# cortina.net
KiCad netlist of a schematic drawn in EAGLE
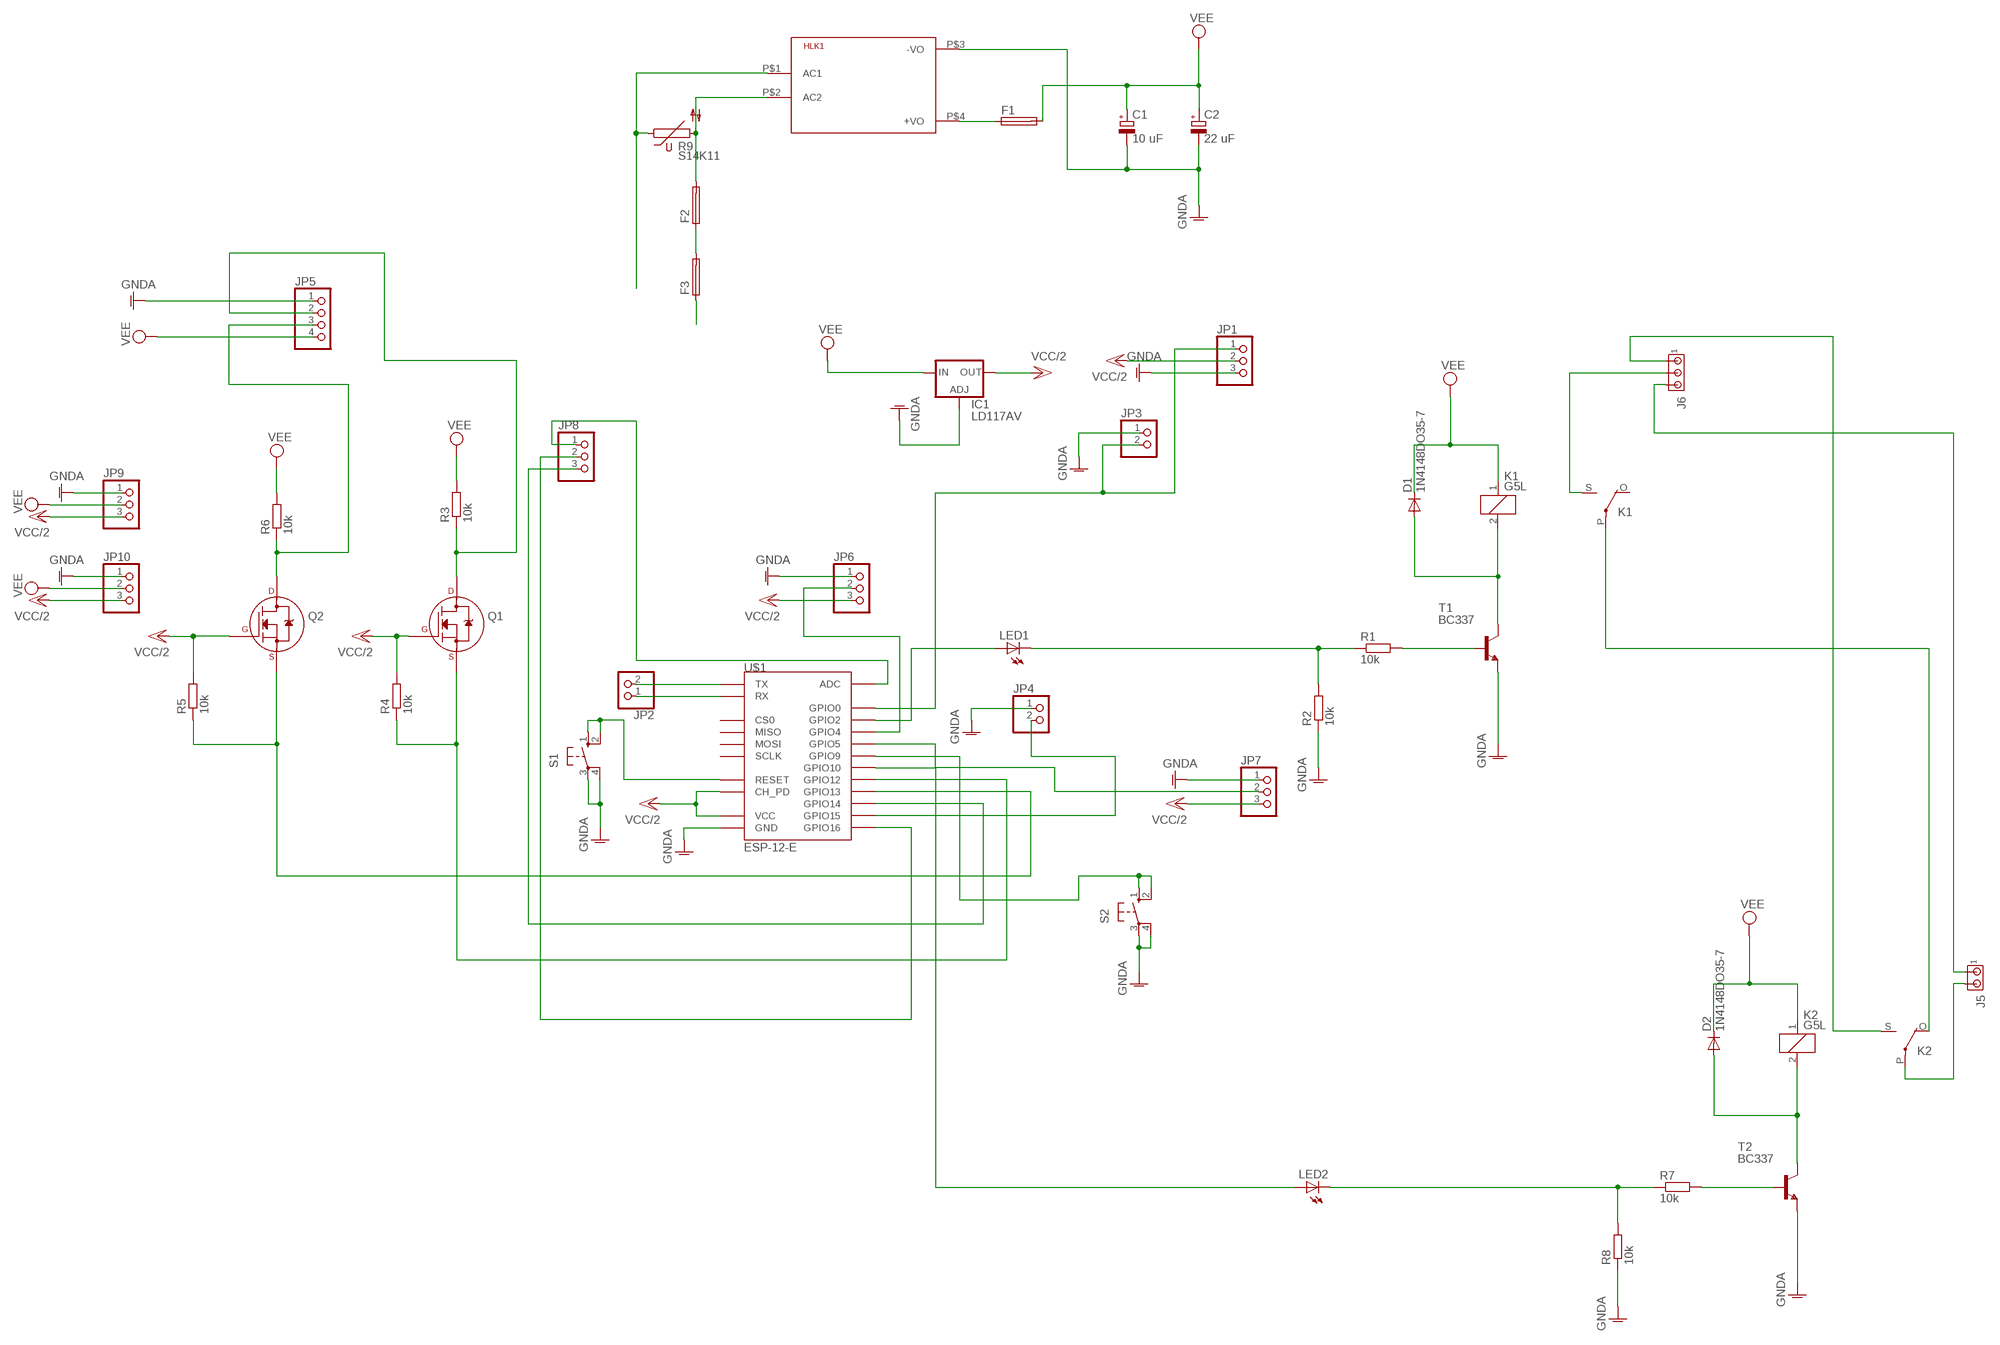
[diagram p0: schematic, sheet 1]

(export (version "E")
  (design (tool "Eeschema 10.0.6"))
  (components
    (comp (ref "C1")
      (value "10 uF")
      (footprint "eagle-import:E1,8-4")
      (libsource (lib "eagle-import") (part "CPOL-EUE1.8-4"))
    )
    (comp (ref "C2")
      (value "22 uF")
      (footprint "eagle-import:E1,8-4")
      (libsource (lib "eagle-import") (part "CPOL-EUE1.8-4"))
    )
    (comp (ref "D1")
      (value "1N4148DO35-7")
      (footprint "eagle-import:DO35-7")
      (libsource (lib "eagle-import") (part "1N4148DO35-7"))
    )
    (comp (ref "D2")
      (value "1N4148DO35-7")
      (footprint "eagle-import:DO35-7")
      (libsource (lib "eagle-import") (part "1N4148DO35-7"))
    )
    (comp (ref "F1")
      (value "GSH15")
      (footprint "eagle-import:GSH15")
      (fields (field (name "MPN") "64900001039"))
      (libsource (lib "eagle-import") (part "GSH15"))
    )
    (comp (ref "F2")
      (value "GSH15")
      (footprint "eagle-import:GSH15")
      (fields (field (name "MPN") "64900001039"))
      (libsource (lib "eagle-import") (part "GSH15"))
    )
    (comp (ref "F3")
      (value "GSH15")
      (footprint "eagle-import:GSH15")
      (fields (field (name "MPN") "64900001039"))
      (libsource (lib "eagle-import") (part "GSH15"))
    )
    (comp (ref "HLK1")
      (value "HLK-PM013W")
      (footprint "eagle-import:HLK-PM01")
      (libsource (lib "eagle-import") (part "HLK-PM013W"))
    )
    (comp (ref "IC1")
      (value "LD117AV")
      (footprint "eagle-import:TO220L1")
      (libsource (lib "eagle-import") (part "LD117A?V"))
    )
    (comp (ref "J5")
      (value "MTA02-156")
      (footprint "eagle-import:1X2MTA")
      (libsource (lib "eagle-import") (part "MTA02-156"))
    )
    (comp (ref "J6")
      (value "MTA03-156")
      (footprint "eagle-import:1X3MTA")
      (libsource (lib "eagle-import") (part "MTA03-156"))
    )
    (comp (ref "JP1")
      (value "PINHD-1X3")
      (footprint "eagle-import:1X03")
      (libsource (lib "eagle-import") (part "PINHD-1X3"))
    )
    (comp (ref "JP2")
      (value "PINHD-1X2")
      (footprint "eagle-import:1X02")
      (libsource (lib "eagle-import") (part "PINHD-1X2"))
    )
    (comp (ref "JP3")
      (value "PINHD-1X2")
      (footprint "eagle-import:1X02")
      (libsource (lib "eagle-import") (part "PINHD-1X2"))
    )
    (comp (ref "JP4")
      (value "PINHD-1X2")
      (footprint "eagle-import:1X02")
      (libsource (lib "eagle-import") (part "PINHD-1X2"))
    )
    (comp (ref "JP5")
      (value "PINHD-1X4")
      (footprint "eagle-import:1X04")
      (libsource (lib "eagle-import") (part "PINHD-1X4"))
    )
    (comp (ref "JP6")
      (value "PINHD-1X3")
      (footprint "eagle-import:1X03")
      (libsource (lib "eagle-import") (part "PINHD-1X3"))
    )
    (comp (ref "JP7")
      (value "PINHD-1X3")
      (footprint "eagle-import:1X03")
      (libsource (lib "eagle-import") (part "PINHD-1X3"))
    )
    (comp (ref "JP8")
      (value "PINHD-1X3")
      (footprint "eagle-import:1X03")
      (libsource (lib "eagle-import") (part "PINHD-1X3"))
    )
    (comp (ref "JP9")
      (value "PINHD-1X3")
      (footprint "eagle-import:1X03")
      (libsource (lib "eagle-import") (part "PINHD-1X3"))
    )
    (comp (ref "JP10")
      (value "PINHD-1X3")
      (footprint "eagle-import:1X03")
      (libsource (lib "eagle-import") (part "PINHD-1X3"))
    )
    (comp (ref "K1")
      (value "G5L")
      (footprint "eagle-import:G5LE")
      (libsource (lib "eagle-import") (part "G5L"))
    )
    (comp (ref "K2")
      (value "G5L")
      (footprint "eagle-import:G5LE")
      (libsource (lib "eagle-import") (part "G5L"))
    )
    (comp (ref "LED1")
      (value "LED5MM")
      (footprint "eagle-import:LED5MM")
      (libsource (lib "eagle-import") (part "LED5MM"))
    )
    (comp (ref "LED2")
      (value "LED5MM")
      (footprint "eagle-import:LED5MM")
      (libsource (lib "eagle-import") (part "LED5MM"))
    )
    (comp (ref "Q1")
      (value "2N7002_TO92")
      (footprint "eagle-import:TO-92")
      (libsource (lib "eagle-import") (part "2N700_TO922"))
    )
    (comp (ref "Q2")
      (value "2N7002_TO92")
      (footprint "eagle-import:TO-92")
      (libsource (lib "eagle-import") (part "2N700_TO922"))
    )
    (comp (ref "R1")
      (value "10k")
      (footprint "eagle-import:0207_7")
      (libsource (lib "eagle-import") (part "R-EU_0207/7"))
    )
    (comp (ref "R2")
      (value "10k")
      (footprint "eagle-import:0207_7")
      (libsource (lib "eagle-import") (part "R-EU_0207/7"))
    )
    (comp (ref "R3")
      (value "10k")
      (footprint "eagle-import:0207_7")
      (libsource (lib "eagle-import") (part "R-EU_0207/7"))
    )
    (comp (ref "R4")
      (value "10k")
      (footprint "eagle-import:0207_7")
      (libsource (lib "eagle-import") (part "R-EU_0207/7"))
    )
    (comp (ref "R5")
      (value "10k")
      (footprint "eagle-import:0207_7")
      (libsource (lib "eagle-import") (part "R-EU_0207/7"))
    )
    (comp (ref "R6")
      (value "10k")
      (footprint "eagle-import:0207_7")
      (libsource (lib "eagle-import") (part "R-EU_0207/7"))
    )
    (comp (ref "R7")
      (value "10k")
      (footprint "eagle-import:0207_7")
      (libsource (lib "eagle-import") (part "R-EU_0207/7"))
    )
    (comp (ref "R8")
      (value "10k")
      (footprint "eagle-import:0207_7")
      (libsource (lib "eagle-import") (part "R-EU_0207/7"))
    )
    (comp (ref "R9")
      (value "S14K11")
      (footprint "eagle-import:S14K11")
      (libsource (lib "eagle-import") (part "S14K11"))
    )
    (comp (ref "S1")
      (value "10-XX")
      (footprint "eagle-import:B3F-10XX")
      (fields (field (name "MPN") "B3F-1000"))
      (libsource (lib "eagle-import") (part "10-XX"))
    )
    (comp (ref "S2")
      (value "10-XX")
      (footprint "eagle-import:B3F-10XX")
      (fields (field (name "MPN") "B3F-1000"))
      (libsource (lib "eagle-import") (part "10-XX"))
    )
    (comp (ref "T1")
      (value "BC337")
      (footprint "eagle-import:TO92")
      (libsource (lib "eagle-import") (part "BC337"))
    )
    (comp (ref "T2")
      (value "BC337")
      (footprint "eagle-import:TO92")
      (libsource (lib "eagle-import") (part "BC337"))
    )
    (comp (ref "U$1")
      (value "ESP-12-E")
      (footprint "eagle-import:ESP-12-E")
      (fields (field (name "SPICEPREFIX") "X"))
      (libsource (lib "eagle-import") (part "ESP-12-E"))
    )
  )
  (nets
    (net (code "1") (name "/N$1") (class "Default")
      (node (ref "HLK1") (pin "P$1") (pinfunction "AC1_P$1") (pintype "bidirectional"))
      (node (ref "J5") (pin "1") (pinfunction "1_1") (pintype "passive"))
      (node (ref "J6") (pin "3") (pinfunction "3_3") (pintype "passive"))
      (node (ref "R9") (pin "1") (pinfunction "1_1") (pintype "passive"))
    )
    (net (code "2") (name "/N$25") (class "Default")
      (node (ref "F3") (pin "1") (pinfunction "1_1") (pintype "passive"))
      (node (ref "J5") (pin "2") (pinfunction "2_2") (pintype "passive"))
      (node (ref "K2") (pin "P") (pinfunction "P_P") (pintype "passive"))
    )
    (net (code "3") (name "GNDA") (class "Default")
      (node (ref "C1") (pin "-") (pinfunction "-_-") (pintype "passive"))
      (node (ref "C2") (pin "-") (pinfunction "-_-") (pintype "passive"))
      (node (ref "HLK1") (pin "P$3") (pinfunction "-VO_P$3") (pintype "bidirectional"))
      (node (ref "IC1") (pin "1") (pinfunction "ADJ_1") (pintype "input"))
      (node (ref "JP1") (pin "3") (pinfunction "3_3") (pintype "passive"))
      (node (ref "JP10") (pin "1") (pinfunction "1_1") (pintype "passive"))
      (node (ref "JP3") (pin "1") (pinfunction "1_1") (pintype "passive"))
      (node (ref "JP4") (pin "1") (pinfunction "1_1") (pintype "passive"))
      (node (ref "JP5") (pin "1") (pinfunction "1_1") (pintype "passive"))
      (node (ref "JP6") (pin "1") (pinfunction "1_1") (pintype "passive"))
      (node (ref "JP7") (pin "1") (pinfunction "1_1") (pintype "passive"))
      (node (ref "JP9") (pin "1") (pinfunction "1_1") (pintype "passive"))
      (node (ref "R2") (pin "1") (pinfunction "1_1") (pintype "passive"))
      (node (ref "R8") (pin "1") (pinfunction "1_1") (pintype "passive"))
      (node (ref "S1") (pin "3") (pinfunction "P_3") (pintype "passive"))
      (node (ref "S1") (pin "4") (pinfunction "P1_4") (pintype "passive"))
      (node (ref "S2") (pin "3") (pinfunction "P_3") (pintype "passive"))
      (node (ref "S2") (pin "4") (pinfunction "P1_4") (pintype "passive"))
      (node (ref "T1") (pin "1") (pinfunction "E_1") (pintype "passive"))
      (node (ref "T2") (pin "1") (pinfunction "E_1") (pintype "passive"))
      (node (ref "U$1") (pin "GND") (pinfunction "GND_GND") (pintype "bidirectional"))
    )
    (net (code "4") (name "Net-(F2-Pad1)") (class "Default")
      (node (ref "F2") (pin "1") (pinfunction "1_1") (pintype "passive"))
      (node (ref "F3") (pin "2") (pinfunction "2_2") (pintype "passive"))
    )
    (net (code "5") (name "Net-(HLK1-+VO)") (class "Default")
      (node (ref "F1") (pin "1") (pinfunction "1_1") (pintype "passive"))
      (node (ref "HLK1") (pin "P$4") (pinfunction "+VO_P$4") (pintype "bidirectional"))
    )
    (net (code "6") (name "Net-(HLK1-AC2)") (class "Default")
      (node (ref "F2") (pin "2") (pinfunction "2_2") (pintype "passive"))
      (node (ref "HLK1") (pin "P$2") (pinfunction "AC2_P$2") (pintype "bidirectional"))
      (node (ref "R9") (pin "2") (pinfunction "2_2") (pintype "passive"))
    )
    (net (code "7") (name "Net-(J6-Pad1)") (class "Default")
      (node (ref "J6") (pin "1") (pinfunction "1_1") (pintype "passive"))
      (node (ref "K2") (pin "S") (pinfunction "S_S") (pintype "passive"))
    )
    (net (code "8") (name "Net-(J6-Pad2)") (class "Default")
      (node (ref "J6") (pin "2") (pinfunction "2_2") (pintype "passive"))
      (node (ref "K1") (pin "S") (pinfunction "S_S") (pintype "passive"))
    )
    (net (code "9") (name "Net-(JP1-Pad1)") (class "Default")
      (node (ref "JP1") (pin "1") (pinfunction "1_1") (pintype "passive"))
      (node (ref "JP3") (pin "2") (pinfunction "2_2") (pintype "passive"))
      (node (ref "U$1") (pin "GPIO0") (pinfunction "GPIO0_GPIO0") (pintype "bidirectional"))
    )
    (net (code "10") (name "Net-(JP2-Pad1)") (class "Default")
      (node (ref "JP2") (pin "1") (pinfunction "1_1") (pintype "passive"))
      (node (ref "U$1") (pin "RX") (pinfunction "RX_RX") (pintype "bidirectional"))
    )
    (net (code "11") (name "Net-(JP2-Pad2)") (class "Default")
      (node (ref "JP2") (pin "2") (pinfunction "2_2") (pintype "passive"))
      (node (ref "U$1") (pin "TX") (pinfunction "TX_TX") (pintype "bidirectional"))
    )
    (net (code "12") (name "Net-(JP4-Pad2)") (class "Default")
      (node (ref "JP4") (pin "2") (pinfunction "2_2") (pintype "passive"))
      (node (ref "U$1") (pin "GPIO15") (pinfunction "GPIO15_GPIO15") (pintype "bidirectional"))
    )
    (net (code "13") (name "Net-(JP6-Pad2)") (class "Default")
      (node (ref "JP6") (pin "2") (pinfunction "2_2") (pintype "passive"))
      (node (ref "U$1") (pin "GPIO4") (pinfunction "GPIO4_GPIO4") (pintype "bidirectional"))
    )
    (net (code "14") (name "Net-(JP7-Pad2)") (class "Default")
      (node (ref "JP7") (pin "2") (pinfunction "2_2") (pintype "passive"))
      (node (ref "LED2") (pin "A") (pinfunction "A_A") (pintype "passive"))
      (node (ref "U$1") (pin "GPIO10") (pinfunction "GPIO10_GPIO10") (pintype "bidirectional"))
      (node (ref "U$1") (pin "GPIO5") (pinfunction "GPIO5_GPIO5") (pintype "bidirectional"))
    )
    (net (code "15") (name "Net-(JP8-Pad1)") (class "Default")
      (node (ref "JP8") (pin "1") (pinfunction "1_1") (pintype "passive"))
      (node (ref "U$1") (pin "ADC") (pinfunction "ADC_ADC") (pintype "bidirectional"))
    )
    (net (code "16") (name "Net-(JP8-Pad2)") (class "Default")
      (node (ref "JP8") (pin "2") (pinfunction "2_2") (pintype "passive"))
      (node (ref "U$1") (pin "GPIO16") (pinfunction "GPIO16_GPIO16") (pintype "bidirectional"))
    )
    (net (code "17") (name "Net-(JP8-Pad3)") (class "Default")
      (node (ref "JP8") (pin "3") (pinfunction "3_3") (pintype "passive"))
      (node (ref "U$1") (pin "GPIO14") (pinfunction "GPIO14_GPIO14") (pintype "bidirectional"))
    )
    (net (code "18") (name "Net-(K1-PadP)") (class "Default")
      (node (ref "K1") (pin "P") (pinfunction "P_P") (pintype "passive"))
      (node (ref "K2") (pin "O") (pinfunction "O_O") (pintype "passive"))
    )
    (net (code "19") (name "Net-(LED1-C)") (class "Default")
      (node (ref "LED1") (pin "K") (pinfunction "C_K") (pintype "passive"))
      (node (ref "R1") (pin "1") (pinfunction "1_1") (pintype "passive"))
      (node (ref "R2") (pin "2") (pinfunction "2_2") (pintype "passive"))
    )
    (net (code "20") (name "Net-(LED1-PadA)") (class "Default")
      (node (ref "LED1") (pin "A") (pinfunction "A_A") (pintype "passive"))
      (node (ref "U$1") (pin "GPIO2") (pinfunction "GPIO2_GPIO2") (pintype "bidirectional"))
    )
    (net (code "21") (name "Net-(LED2-C)") (class "Default")
      (node (ref "LED2") (pin "K") (pinfunction "C_K") (pintype "passive"))
      (node (ref "R7") (pin "1") (pinfunction "1_1") (pintype "passive"))
      (node (ref "R8") (pin "2") (pinfunction "2_2") (pintype "passive"))
    )
    (net (code "22") (name "Net-(Q1-D)") (class "Default")
      (node (ref "JP5") (pin "2") (pinfunction "2_2") (pintype "passive"))
      (node (ref "Q1") (pin "3") (pinfunction "D_3") (pintype "bidirectional"))
      (node (ref "R3") (pin "1") (pinfunction "1_1") (pintype "passive"))
    )
    (net (code "23") (name "Net-(Q1-S)") (class "Default")
      (node (ref "Q1") (pin "1") (pinfunction "S_1") (pintype "bidirectional"))
      (node (ref "R4") (pin "1") (pinfunction "1_1") (pintype "passive"))
      (node (ref "U$1") (pin "GPIO12") (pinfunction "GPIO12_GPIO12") (pintype "bidirectional"))
    )
    (net (code "24") (name "Net-(Q2-D)") (class "Default")
      (node (ref "JP5") (pin "3") (pinfunction "3_3") (pintype "passive"))
      (node (ref "Q2") (pin "3") (pinfunction "D_3") (pintype "bidirectional"))
      (node (ref "R6") (pin "1") (pinfunction "1_1") (pintype "passive"))
    )
    (net (code "25") (name "Net-(Q2-S)") (class "Default")
      (node (ref "Q2") (pin "1") (pinfunction "S_1") (pintype "bidirectional"))
      (node (ref "R5") (pin "1") (pinfunction "1_1") (pintype "passive"))
      (node (ref "U$1") (pin "GPIO13") (pinfunction "GPIO13_GPIO13") (pintype "bidirectional"))
    )
    (net (code "26") (name "Net-(S1-S)") (class "Default")
      (node (ref "S1") (pin "1") (pinfunction "S_1") (pintype "passive"))
      (node (ref "S1") (pin "2") (pinfunction "S1_2") (pintype "passive"))
      (node (ref "U$1") (pin "RESET") (pinfunction "RESET_RESET") (pintype "bidirectional"))
    )
    (net (code "27") (name "Net-(S2-S)") (class "Default")
      (node (ref "S2") (pin "1") (pinfunction "S_1") (pintype "passive"))
      (node (ref "S2") (pin "2") (pinfunction "S1_2") (pintype "passive"))
      (node (ref "U$1") (pin "GPIO9") (pinfunction "GPIO9_GPIO9") (pintype "bidirectional"))
    )
    (net (code "28") (name "Net-(T1-B)") (class "Default")
      (node (ref "R1") (pin "2") (pinfunction "2_2") (pintype "passive"))
      (node (ref "T1") (pin "2") (pinfunction "B_2") (pintype "passive"))
    )
    (net (code "29") (name "Net-(T1-C)") (class "Default")
      (node (ref "D1") (pin "A") (pinfunction "A_A") (pintype "passive"))
      (node (ref "K1") (pin "2") (pinfunction "2_2") (pintype "passive"))
      (node (ref "T1") (pin "3") (pinfunction "C_3") (pintype "passive"))
    )
    (net (code "30") (name "Net-(T2-B)") (class "Default")
      (node (ref "R7") (pin "2") (pinfunction "2_2") (pintype "passive"))
      (node (ref "T2") (pin "2") (pinfunction "B_2") (pintype "passive"))
    )
    (net (code "31") (name "Net-(T2-C)") (class "Default")
      (node (ref "D2") (pin "A") (pinfunction "A_A") (pintype "passive"))
      (node (ref "K2") (pin "2") (pinfunction "2_2") (pintype "passive"))
      (node (ref "T2") (pin "3") (pinfunction "C_3") (pintype "passive"))
    )
    (net (code "32") (name "VCC{slash}2") (class "Default")
      (node (ref "IC1") (pin "2") (pinfunction "OUT_2") (pintype "passive"))
      (node (ref "JP1") (pin "2") (pinfunction "2_2") (pintype "passive"))
      (node (ref "JP10") (pin "3") (pinfunction "3_3") (pintype "passive"))
      (node (ref "JP6") (pin "3") (pinfunction "3_3") (pintype "passive"))
      (node (ref "JP7") (pin "3") (pinfunction "3_3") (pintype "passive"))
      (node (ref "JP9") (pin "3") (pinfunction "3_3") (pintype "passive"))
      (node (ref "Q1") (pin "2") (pinfunction "G_2") (pintype "tri_state"))
      (node (ref "Q2") (pin "2") (pinfunction "G_2") (pintype "tri_state"))
      (node (ref "R4") (pin "2") (pinfunction "2_2") (pintype "passive"))
      (node (ref "R5") (pin "2") (pinfunction "2_2") (pintype "passive"))
      (node (ref "U$1") (pin "CH_PD") (pinfunction "CH_PD_CH_PD") (pintype "bidirectional"))
      (node (ref "U$1") (pin "VCC") (pinfunction "VCC_VCC") (pintype "bidirectional"))
    )
    (net (code "33") (name "VEE") (class "Default")
      (node (ref "C1") (pin "+") (pinfunction "+_+") (pintype "passive"))
      (node (ref "C2") (pin "+") (pinfunction "+_+") (pintype "passive"))
      (node (ref "D1") (pin "C") (pinfunction "C_C") (pintype "passive"))
      (node (ref "D2") (pin "C") (pinfunction "C_C") (pintype "passive"))
      (node (ref "F1") (pin "2") (pinfunction "2_2") (pintype "passive"))
      (node (ref "IC1") (pin "3") (pinfunction "IN_3") (pintype "input"))
      (node (ref "JP10") (pin "2") (pinfunction "2_2") (pintype "passive"))
      (node (ref "JP5") (pin "4") (pinfunction "4_4") (pintype "passive"))
      (node (ref "JP9") (pin "2") (pinfunction "2_2") (pintype "passive"))
      (node (ref "K1") (pin "1") (pinfunction "1_1") (pintype "passive"))
      (node (ref "K2") (pin "1") (pinfunction "1_1") (pintype "passive"))
      (node (ref "R3") (pin "2") (pinfunction "2_2") (pintype "passive"))
      (node (ref "R6") (pin "2") (pinfunction "2_2") (pintype "passive"))
    )
    (net (code "34") (name "unconnected-(K1-PadO)") (class "Default")
      (node (ref "K1") (pin "O") (pinfunction "O_O") (pintype "passive"))
    )
    (net (code "35") (name "unconnected-(U$1-PadCS0)") (class "Default")
      (node (ref "U$1") (pin "CS0") (pinfunction "CS0_CS0") (pintype "bidirectional"))
    )
    (net (code "36") (name "unconnected-(U$1-PadMISO)") (class "Default")
      (node (ref "U$1") (pin "MISO") (pinfunction "MISO_MISO") (pintype "bidirectional"))
    )
    (net (code "37") (name "unconnected-(U$1-PadMOSI)") (class "Default")
      (node (ref "U$1") (pin "MOSI") (pinfunction "MOSI_MOSI") (pintype "bidirectional"))
    )
    (net (code "38") (name "unconnected-(U$1-PadSCLK)") (class "Default")
      (node (ref "U$1") (pin "SCLK") (pinfunction "SCLK_SCLK") (pintype "bidirectional"))
    )
  )
)
